# Front_panel_owon_extended.net
KiCad netlist of a schematic drawn in EAGLE
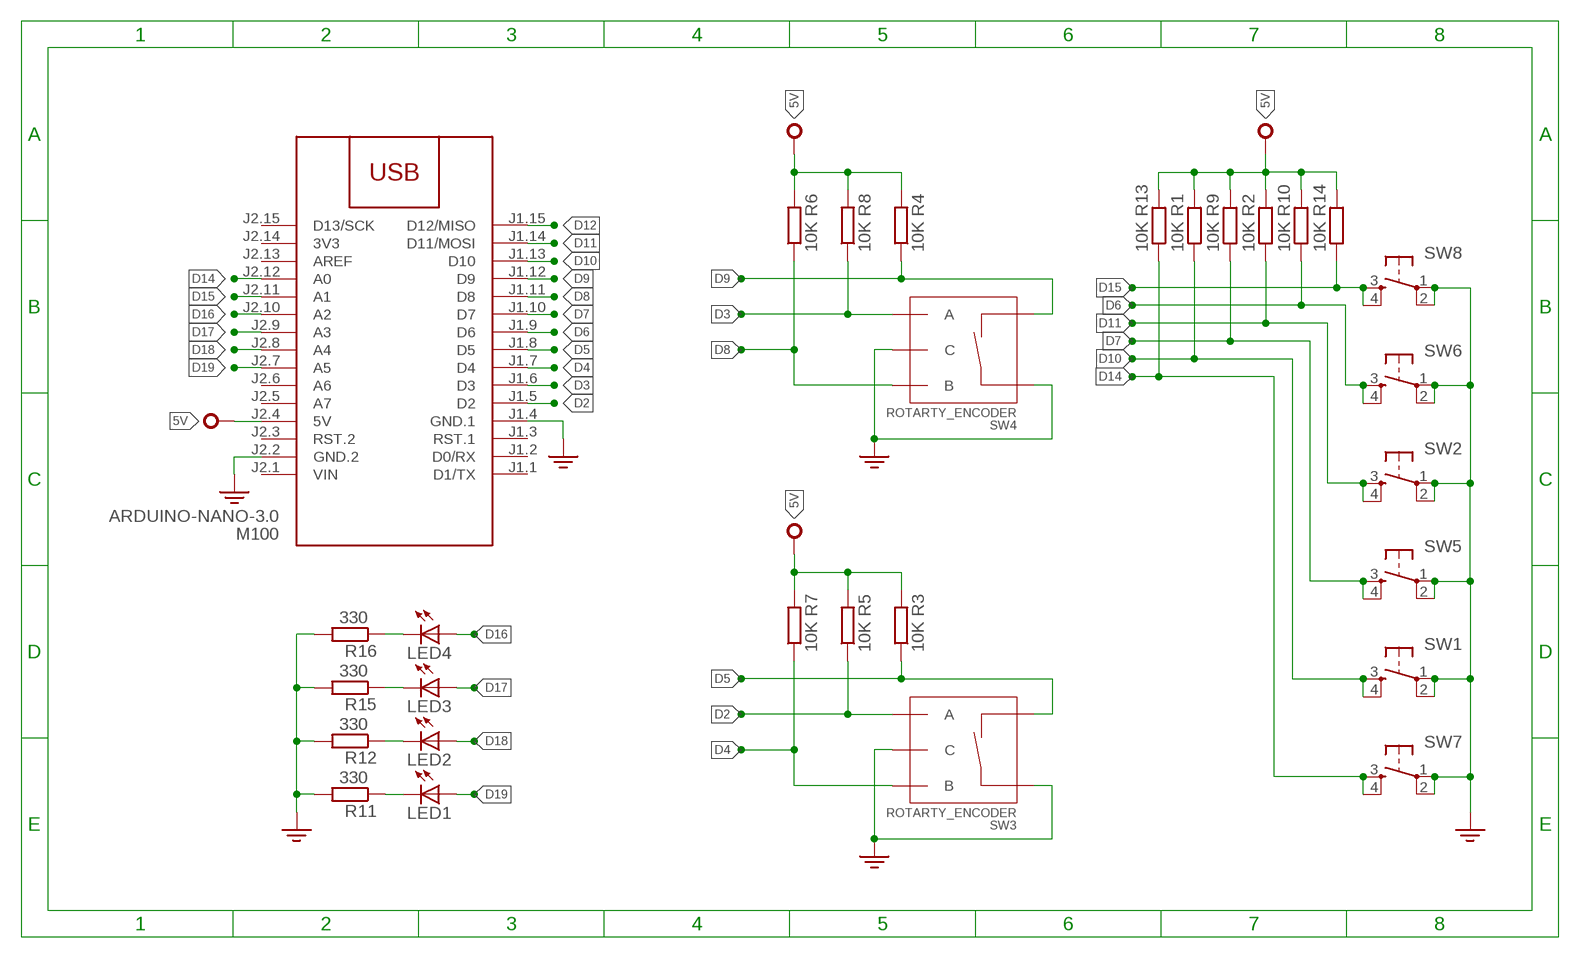
[diagram p0: schematic, sheet 1]

(export (version "E")
  (design (tool "Eeschema 10.0.6"))
  (components
    (comp (ref "LED1")
      (value "LED5MM")
      (footprint "eagle-import:LED5MM")
      (libsource (lib "eagle-import") (part "LED5MM"))
    )
    (comp (ref "LED2")
      (value "LED5MM")
      (footprint "eagle-import:LED5MM")
      (libsource (lib "eagle-import") (part "LED5MM"))
    )
    (comp (ref "LED3")
      (value "LED5MM")
      (footprint "eagle-import:LED5MM")
      (libsource (lib "eagle-import") (part "LED5MM"))
    )
    (comp (ref "LED4")
      (value "LED5MM")
      (footprint "eagle-import:LED5MM")
      (libsource (lib "eagle-import") (part "LED5MM"))
    )
    (comp (ref "M100")
      (value "ARDUINO-NANO-3.0")
      (footprint "eagle-import:ARDUINO-NANO-3.0")
      (libsource (lib "eagle-import") (part "ARDUINO-NANO-3.0"))
    )
    (comp (ref "R1")
      (value "10K")
      (footprint "eagle-import:0204_7")
      (libsource (lib "eagle-import") (part "R-EU_0204/7"))
    )
    (comp (ref "R2")
      (value "10K")
      (footprint "eagle-import:0204_7")
      (libsource (lib "eagle-import") (part "R-EU_0204/7"))
    )
    (comp (ref "R3")
      (value "10K")
      (footprint "eagle-import:0204_7")
      (libsource (lib "eagle-import") (part "R-EU_0204/7"))
    )
    (comp (ref "R4")
      (value "10K")
      (footprint "eagle-import:0204_7")
      (libsource (lib "eagle-import") (part "R-EU_0204/7"))
    )
    (comp (ref "R5")
      (value "10K")
      (footprint "eagle-import:0204_7")
      (libsource (lib "eagle-import") (part "R-EU_0204/7"))
    )
    (comp (ref "R6")
      (value "10K")
      (footprint "eagle-import:0204_7")
      (libsource (lib "eagle-import") (part "R-EU_0204/7"))
    )
    (comp (ref "R7")
      (value "10K")
      (footprint "eagle-import:0204_7")
      (libsource (lib "eagle-import") (part "R-EU_0204/7"))
    )
    (comp (ref "R8")
      (value "10K")
      (footprint "eagle-import:0204_7")
      (libsource (lib "eagle-import") (part "R-EU_0204/7"))
    )
    (comp (ref "R9")
      (value "10K")
      (footprint "eagle-import:0204_7")
      (libsource (lib "eagle-import") (part "R-EU_0204/7"))
    )
    (comp (ref "R10")
      (value "10K")
      (footprint "eagle-import:0204_7")
      (libsource (lib "eagle-import") (part "R-EU_0204/7"))
    )
    (comp (ref "R11")
      (value "330")
      (footprint "eagle-import:0204_7")
      (libsource (lib "eagle-import") (part "R-EU_0204/7"))
    )
    (comp (ref "R12")
      (value "330")
      (footprint "eagle-import:0204_7")
      (libsource (lib "eagle-import") (part "R-EU_0204/7"))
    )
    (comp (ref "R13")
      (value "10K")
      (footprint "eagle-import:0204_7")
      (libsource (lib "eagle-import") (part "R-EU_0204/7"))
    )
    (comp (ref "R14")
      (value "10K")
      (footprint "eagle-import:0204_7")
      (libsource (lib "eagle-import") (part "R-EU_0204/7"))
    )
    (comp (ref "R15")
      (value "330")
      (footprint "eagle-import:0204_7")
      (libsource (lib "eagle-import") (part "R-EU_0204/7"))
    )
    (comp (ref "R16")
      (value "330")
      (footprint "eagle-import:0204_7")
      (libsource (lib "eagle-import") (part "R-EU_0204/7"))
    )
    (comp (ref "SW1")
      (value "TACTILE-SWITCH-PTH")
      (footprint "eagle-import:TAC-SWITCH-PTH")
      (libsource (lib "eagle-import") (part "TACTILE-SWITCH-PTH"))
    )
    (comp (ref "SW2")
      (value "TACTILE-SWITCH-PTH")
      (footprint "eagle-import:TAC-SWITCH-PTH")
      (libsource (lib "eagle-import") (part "TACTILE-SWITCH-PTH"))
    )
    (comp (ref "SW3")
      (value "ROTARTY_ENCODER")
      (footprint "eagle-import:ROTARY_ENC_PLAIN")
      (libsource (lib "eagle-import") (part "ROTARTY_ENCODER"))
    )
    (comp (ref "SW4")
      (value "ROTARTY_ENCODER")
      (footprint "eagle-import:ROTARY_ENC_PLAIN")
      (libsource (lib "eagle-import") (part "ROTARTY_ENCODER"))
    )
    (comp (ref "SW5")
      (value "TACTILE-SWITCH-PTH")
      (footprint "eagle-import:TAC-SWITCH-PTH")
      (libsource (lib "eagle-import") (part "TACTILE-SWITCH-PTH"))
    )
    (comp (ref "SW6")
      (value "TACTILE-SWITCH-PTH")
      (footprint "eagle-import:TAC-SWITCH-PTH")
      (libsource (lib "eagle-import") (part "TACTILE-SWITCH-PTH"))
    )
    (comp (ref "SW7")
      (value "TACTILE-SWITCH-PTH")
      (footprint "eagle-import:TAC-SWITCH-PTH")
      (libsource (lib "eagle-import") (part "TACTILE-SWITCH-PTH"))
    )
    (comp (ref "SW8")
      (value "TACTILE-SWITCH-PTH")
      (footprint "eagle-import:TAC-SWITCH-PTH")
      (libsource (lib "eagle-import") (part "TACTILE-SWITCH-PTH"))
    )
  )
  (nets
    (net (code "1") (name "/3V3") (class "Default")
      (node (ref "M100") (pin "J2.14") (pinfunction "3V3_J2.14") (pintype "power_in"))
    )
    (net (code "2") (name "/VIN") (class "Default")
      (node (ref "M100") (pin "J2.1") (pinfunction "VIN_J2.1") (pintype "power_in"))
    )
    (net (code "3") (name "5V") (class "Default")
      (node (ref "M100") (pin "J2.4") (pinfunction "5V_J2.4") (pintype "power_in"))
      (node (ref "R1") (pin "2") (pinfunction "2_2") (pintype "passive"))
      (node (ref "R10") (pin "2") (pinfunction "2_2") (pintype "passive"))
      (node (ref "R13") (pin "2") (pinfunction "2_2") (pintype "passive"))
      (node (ref "R14") (pin "2") (pinfunction "2_2") (pintype "passive"))
      (node (ref "R2") (pin "2") (pinfunction "2_2") (pintype "passive"))
      (node (ref "R3") (pin "2") (pinfunction "2_2") (pintype "passive"))
      (node (ref "R4") (pin "2") (pinfunction "2_2") (pintype "passive"))
      (node (ref "R5") (pin "2") (pinfunction "2_2") (pintype "passive"))
      (node (ref "R6") (pin "2") (pinfunction "2_2") (pintype "passive"))
      (node (ref "R7") (pin "2") (pinfunction "2_2") (pintype "passive"))
      (node (ref "R8") (pin "2") (pinfunction "2_2") (pintype "passive"))
      (node (ref "R9") (pin "2") (pinfunction "2_2") (pintype "passive"))
    )
    (net (code "4") (name "D2") (class "Default")
      (node (ref "M100") (pin "J1.5") (pinfunction "D2_J1.5") (pintype "bidirectional"))
      (node (ref "R5") (pin "1") (pinfunction "1_1") (pintype "passive"))
      (node (ref "SW3") (pin "A") (pinfunction "A_A") (pintype "bidirectional"))
    )
    (net (code "5") (name "D3") (class "Default")
      (node (ref "M100") (pin "J1.6") (pinfunction "D3_J1.6") (pintype "bidirectional"))
      (node (ref "R8") (pin "1") (pinfunction "1_1") (pintype "passive"))
      (node (ref "SW4") (pin "A") (pinfunction "A_A") (pintype "bidirectional"))
    )
    (net (code "6") (name "D4") (class "Default")
      (node (ref "M100") (pin "J1.7") (pinfunction "D4_J1.7") (pintype "bidirectional"))
      (node (ref "R7") (pin "1") (pinfunction "1_1") (pintype "passive"))
      (node (ref "SW3") (pin "B") (pinfunction "B_B") (pintype "bidirectional"))
    )
    (net (code "7") (name "D5") (class "Default")
      (node (ref "M100") (pin "J1.8") (pinfunction "D5_J1.8") (pintype "bidirectional"))
      (node (ref "R3") (pin "1") (pinfunction "1_1") (pintype "passive"))
      (node (ref "SW3") (pin "SW-") (pinfunction "SW-_SW-") (pintype "bidirectional"))
    )
    (net (code "8") (name "D6") (class "Default")
      (node (ref "M100") (pin "J1.9") (pinfunction "D6_J1.9") (pintype "bidirectional"))
      (node (ref "R10") (pin "1") (pinfunction "1_1") (pintype "passive"))
      (node (ref "SW6") (pin "3") (pinfunction "3_3") (pintype "passive"))
      (node (ref "SW6") (pin "4") (pinfunction "4_4") (pintype "passive"))
    )
    (net (code "9") (name "D7") (class "Default")
      (node (ref "M100") (pin "J1.10") (pinfunction "D7_J1.10") (pintype "bidirectional"))
      (node (ref "R9") (pin "1") (pinfunction "1_1") (pintype "passive"))
      (node (ref "SW5") (pin "3") (pinfunction "3_3") (pintype "passive"))
      (node (ref "SW5") (pin "4") (pinfunction "4_4") (pintype "passive"))
    )
    (net (code "10") (name "D8") (class "Default")
      (node (ref "M100") (pin "J1.11") (pinfunction "D8_J1.11") (pintype "bidirectional"))
      (node (ref "R6") (pin "1") (pinfunction "1_1") (pintype "passive"))
      (node (ref "SW4") (pin "B") (pinfunction "B_B") (pintype "bidirectional"))
    )
    (net (code "11") (name "D9") (class "Default")
      (node (ref "M100") (pin "J1.12") (pinfunction "D9_J1.12") (pintype "bidirectional"))
      (node (ref "R4") (pin "1") (pinfunction "1_1") (pintype "passive"))
      (node (ref "SW4") (pin "SW-") (pinfunction "SW-_SW-") (pintype "bidirectional"))
    )
    (net (code "12") (name "D10") (class "Default")
      (node (ref "M100") (pin "J1.13") (pinfunction "D10_J1.13") (pintype "bidirectional"))
      (node (ref "R1") (pin "1") (pinfunction "1_1") (pintype "passive"))
      (node (ref "SW1") (pin "3") (pinfunction "3_3") (pintype "passive"))
      (node (ref "SW1") (pin "4") (pinfunction "4_4") (pintype "passive"))
    )
    (net (code "13") (name "D11") (class "Default")
      (node (ref "M100") (pin "J1.14") (pinfunction "D11/MOSI_J1.14") (pintype "bidirectional"))
      (node (ref "R2") (pin "1") (pinfunction "1_1") (pintype "passive"))
      (node (ref "SW2") (pin "3") (pinfunction "3_3") (pintype "passive"))
      (node (ref "SW2") (pin "4") (pinfunction "4_4") (pintype "passive"))
    )
    (net (code "14") (name "D12") (class "Default")
      (node (ref "M100") (pin "J1.15") (pinfunction "D12/MISO_J1.15") (pintype "bidirectional"))
    )
    (net (code "15") (name "D14") (class "Default")
      (node (ref "M100") (pin "J2.12") (pinfunction "A0_J2.12") (pintype "bidirectional"))
      (node (ref "R13") (pin "1") (pinfunction "1_1") (pintype "passive"))
      (node (ref "SW7") (pin "3") (pinfunction "3_3") (pintype "passive"))
      (node (ref "SW7") (pin "4") (pinfunction "4_4") (pintype "passive"))
    )
    (net (code "16") (name "D15") (class "Default")
      (node (ref "M100") (pin "J2.11") (pinfunction "A1_J2.11") (pintype "bidirectional"))
      (node (ref "R14") (pin "1") (pinfunction "1_1") (pintype "passive"))
      (node (ref "SW8") (pin "3") (pinfunction "3_3") (pintype "passive"))
      (node (ref "SW8") (pin "4") (pinfunction "4_4") (pintype "passive"))
    )
    (net (code "17") (name "D16") (class "Default")
      (node (ref "LED4") (pin "A") (pinfunction "A_A") (pintype "passive"))
      (node (ref "M100") (pin "J2.10") (pinfunction "A2_J2.10") (pintype "bidirectional"))
    )
    (net (code "18") (name "D17") (class "Default")
      (node (ref "LED3") (pin "A") (pinfunction "A_A") (pintype "passive"))
      (node (ref "M100") (pin "J2.9") (pinfunction "A3_J2.9") (pintype "bidirectional"))
    )
    (net (code "19") (name "D18") (class "Default")
      (node (ref "LED2") (pin "A") (pinfunction "A_A") (pintype "passive"))
      (node (ref "M100") (pin "J2.8") (pinfunction "A4_J2.8") (pintype "bidirectional"))
    )
    (net (code "20") (name "D19") (class "Default")
      (node (ref "LED1") (pin "A") (pinfunction "A_A") (pintype "passive"))
      (node (ref "M100") (pin "J2.7") (pinfunction "A5_J2.7") (pintype "bidirectional"))
    )
    (net (code "21") (name "GND2") (class "Default")
      (node (ref "M100") (pin "J1.4") (pinfunction "GND.1_J1.4") (pintype "power_in"))
      (node (ref "M100") (pin "J2.2") (pinfunction "GND.2_J2.2") (pintype "power_in"))
      (node (ref "R11") (pin "2") (pinfunction "2_2") (pintype "passive"))
      (node (ref "R12") (pin "2") (pinfunction "2_2") (pintype "passive"))
      (node (ref "R15") (pin "2") (pinfunction "2_2") (pintype "passive"))
      (node (ref "R16") (pin "2") (pinfunction "2_2") (pintype "passive"))
      (node (ref "SW1") (pin "1") (pinfunction "1_1") (pintype "passive"))
      (node (ref "SW1") (pin "2") (pinfunction "2_2") (pintype "passive"))
      (node (ref "SW2") (pin "1") (pinfunction "1_1") (pintype "passive"))
      (node (ref "SW2") (pin "2") (pinfunction "2_2") (pintype "passive"))
      (node (ref "SW3") (pin "C") (pinfunction "C_C") (pintype "bidirectional"))
      (node (ref "SW3") (pin "SW+") (pinfunction "SW+_SW+") (pintype "bidirectional"))
      (node (ref "SW4") (pin "C") (pinfunction "C_C") (pintype "bidirectional"))
      (node (ref "SW4") (pin "SW+") (pinfunction "SW+_SW+") (pintype "bidirectional"))
      (node (ref "SW5") (pin "1") (pinfunction "1_1") (pintype "passive"))
      (node (ref "SW5") (pin "2") (pinfunction "2_2") (pintype "passive"))
      (node (ref "SW6") (pin "1") (pinfunction "1_1") (pintype "passive"))
      (node (ref "SW6") (pin "2") (pinfunction "2_2") (pintype "passive"))
      (node (ref "SW7") (pin "1") (pinfunction "1_1") (pintype "passive"))
      (node (ref "SW7") (pin "2") (pinfunction "2_2") (pintype "passive"))
      (node (ref "SW8") (pin "1") (pinfunction "1_1") (pintype "passive"))
      (node (ref "SW8") (pin "2") (pinfunction "2_2") (pintype "passive"))
    )
    (net (code "22") (name "Net-(LED1-C)") (class "Default")
      (node (ref "LED1") (pin "K") (pinfunction "C_K") (pintype "passive"))
      (node (ref "R11") (pin "1") (pinfunction "1_1") (pintype "passive"))
    )
    (net (code "23") (name "Net-(LED2-C)") (class "Default")
      (node (ref "LED2") (pin "K") (pinfunction "C_K") (pintype "passive"))
      (node (ref "R12") (pin "1") (pinfunction "1_1") (pintype "passive"))
    )
    (net (code "24") (name "Net-(LED3-C)") (class "Default")
      (node (ref "LED3") (pin "K") (pinfunction "C_K") (pintype "passive"))
      (node (ref "R15") (pin "1") (pinfunction "1_1") (pintype "passive"))
    )
    (net (code "25") (name "Net-(LED4-C)") (class "Default")
      (node (ref "LED4") (pin "K") (pinfunction "C_K") (pintype "passive"))
      (node (ref "R16") (pin "1") (pinfunction "1_1") (pintype "passive"))
    )
    (net (code "26") (name "unconnected-(M100-A6-PadJ2.6)") (class "Default")
      (node (ref "M100") (pin "J2.6") (pinfunction "A6_J2.6") (pintype "bidirectional"))
    )
    (net (code "27") (name "unconnected-(M100-A7-PadJ2.5)") (class "Default")
      (node (ref "M100") (pin "J2.5") (pinfunction "A7_J2.5") (pintype "bidirectional"))
    )
    (net (code "28") (name "unconnected-(M100-AREF-PadJ2.13)") (class "Default")
      (node (ref "M100") (pin "J2.13") (pinfunction "AREF_J2.13") (pintype "bidirectional"))
    )
    (net (code "29") (name "unconnected-(M100-D0{slash}RX-PadJ1.2)") (class "Default")
      (node (ref "M100") (pin "J1.2") (pinfunction "D0/RX_J1.2") (pintype "bidirectional"))
    )
    (net (code "30") (name "unconnected-(M100-D1{slash}TX-PadJ1.1)") (class "Default")
      (node (ref "M100") (pin "J1.1") (pinfunction "D1/TX_J1.1") (pintype "bidirectional"))
    )
    (net (code "31") (name "unconnected-(M100-D13{slash}SCK-PadJ2.15)") (class "Default")
      (node (ref "M100") (pin "J2.15") (pinfunction "D13/SCK_J2.15") (pintype "bidirectional"))
    )
    (net (code "32") (name "unconnected-(M100-RST.1-PadJ1.3)") (class "Default")
      (node (ref "M100") (pin "J1.3") (pinfunction "RST.1_J1.3") (pintype "bidirectional"))
    )
    (net (code "33") (name "unconnected-(M100-RST.2-PadJ2.3)") (class "Default")
      (node (ref "M100") (pin "J2.3") (pinfunction "RST.2_J2.3") (pintype "bidirectional"))
    )
  )
)
